# 3_3V_to_DDR4_VDD.net
KiCad netlist of a schematic drawn in Altium Designer
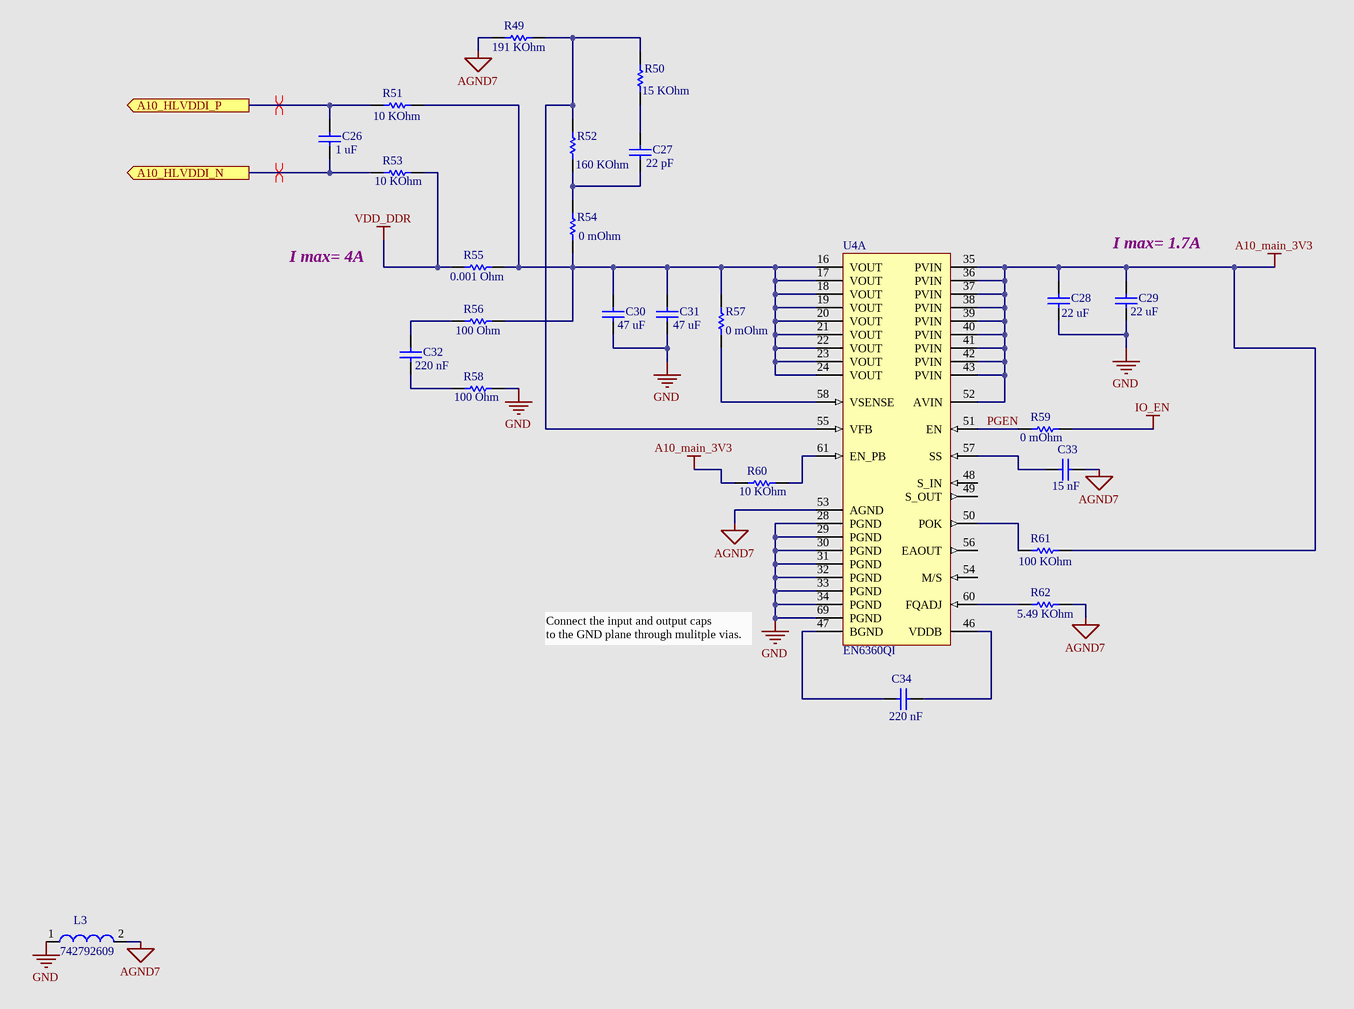
[diagram p0: 3.3V_to_DDR4_VDD.SchDoc]

(export (version "E")
  (design (tool "Eeschema 10.0.6"))
  (components
    (comp (ref "C26")
      (value "CGB2A1X5R1E105K033BC")
      (footprint "CAPC1005X33X10LL5")
      (description "Chip Capacitor, 1 uF, +/- 10%, 25 V, -55 to 85 degC, 0402 (1005 Metric), RoHS, Tape and Reel")
      (fields (field (name "TOLERANCE") "10%") (field (name "CAPACITANCE") "1 uF"))
      (libsource (lib "") (part "CAP-NP-2_1"))
    )
    (comp (ref "C27")
      (value "C1005C0G1H220J050BA")
      (footprint "CAPC1005X55X10LL05")
      (description "Chip Capacitor, 22 pF, +/- 5%, 50 V, -55 to 125 degC, 0402 (1005 Metric), RoHS, Tape and Reel")
      (fields (field (name "TOLERANCE") "5%") (field (name "CAPACITANCE") "22 pF"))
      (libsource (lib "Altium Content Vault") (part "CAP-NP-2"))
    )
    (comp (ref "C28")
      (value "GRM31CR61E226KE15L")
      (footprint "CAPC3216X180X55ML20T25")
      (description "Chip Capacitor, 22 uF, +/- 10%, 25 V, -55 to 85 degC, 1206 (3216 Metric), RoHS, Tape and Reel")
      (fields (field (name "TOLERANCE") "10%") (field (name "CAPACITANCE") "22 uF"))
      (libsource (lib "Altium Content Vault") (part "CAP-NP-2"))
    )
    (comp (ref "C29")
      (value "GRM31CR61E226KE15L")
      (footprint "CAPC3216X180X55ML20T25")
      (description "Chip Capacitor, 22 uF, +/- 10%, 25 V, -55 to 85 degC, 1206 (3216 Metric), RoHS, Tape and Reel")
      (fields (field (name "TOLERANCE") "10%") (field (name "CAPACITANCE") "22 uF"))
      (libsource (lib "Altium Content Vault") (part "CAP-NP-2"))
    )
    (comp (ref "C30")
      (value "C3216X5R1A476M160AB")
      (footprint "CAPC3216X180X20ML20")
      (description "Chip Capacitor, 47 uF, +/- 20%, 10 V, -55 to 85 degC, 1206 (3216 Metric), RoHS, Tape and Reel")
      (fields (field (name "TOLERANCE") "20%") (field (name "CAPACITANCE") "47 uF"))
      (libsource (lib "") (part "CAP-NP-2_1"))
    )
    (comp (ref "C31")
      (value "C3216X5R1A476M160AB")
      (footprint "CAPC3216X180X20ML20")
      (description "Chip Capacitor, 47 uF, +/- 20%, 10 V, -55 to 85 degC, 1206 (3216 Metric), RoHS, Tape and Reel")
      (fields (field (name "TOLERANCE") "20%") (field (name "CAPACITANCE") "47 uF"))
      (libsource (lib "") (part "CAP-NP-2_1"))
    )
    (comp (ref "C32")
      (value "GRM155R61A224KE19D")
      (footprint "CAPC1005X55X25NL05T10")
      (description "Chip Capacitor, 220 nF, +/- 10%, 10 V, -55 to 85 degC, 0402 (1005 Metric), RoHS, Tape and Reel")
      (fields
        (field (name "TOLERANCE") "10%")
        (field (name "CAPACITANCE") "220 nF")
        (field (name "MANUFACTURER") "Basic Passives")
      )
      (libsource (lib "Altium Content Vault") (part "CAP-NP-2"))
    )
    (comp (ref "C33")
      (value "VJ0402Y153JXQPW1BC")
      (footprint "CAPC1005X55X23ML05T8")
      (description "Chip Capacitor, 15 nF, +/- 5%, 10 V, -55 to 125 degC, 0402 (1005 Metric), RoHS, Tape and Reel")
      (fields (field (name "CAPACITANCE") "15 nF") (field (name "TOLERANCE") "5%"))
      (libsource (lib "Altium Content Vault") (part "CAP-NP-2"))
    )
    (comp (ref "C34")
      (value "GRM155R61A224KE19D")
      (footprint "CAPC1005X55X25NL05T10")
      (description "Chip Capacitor, 220 nF, +/- 10%, 10 V, -55 to 85 degC, 0402 (1005 Metric), RoHS, Tape and Reel")
      (fields
        (field (name "TOLERANCE") "10%")
        (field (name "CAPACITANCE") "220 nF")
        (field (name "MANUFACTURER") "Basic Passives")
      )
      (libsource (lib "Altium Content Vault") (part "CAP-NP-2"))
    )
    (comp (ref "L3")
      (value "742792609")
      (footprint "SMD-0603")
      (description "SMD EMI Suppression Ferrite Bead WE-CBF, Z = 30 Ohm")
      (libsource (lib "Altium Content Vault") (part "CMP-0220-00193-1"))
    )
    (comp (ref "R49")
      (value "CRCW0402191KFKED")
      (footprint "RESC1005X40X25LL05T05")
      (description "Chip Resistor, 191 KOhm, +/- 1%, 63 mW, -55 to 155 degC, 0402 (1005 Metric), RoHS, Tape and Reel")
      (fields
        (field (name "TOLERANCE") "1%")
        (field (name "RESISTANCE") "191 KOhm")
        (field (name "MANUFACTURER") "Basic Passives")
      )
      (libsource (lib "Altium Content Vault") (part "RES-2"))
    )
    (comp (ref "R50")
      (value "ERJ-2RKF1502X")
      (footprint "RESC1005X40X25ML05T05")
      (description "Chip Resistor, 15 KOhm, +/- 1%, 100 mW, -55 to 155 degC, 0402 (1005 Metric), RoHS, Tape and Reel")
      (fields
        (field (name "RESISTANCE") "15 KOhm")
        (field (name "TOLERANCE") "1%")
        (field (name "MANUFACTURER") "Basic Passives")
      )
      (libsource (lib "Altium Content Vault") (part "RES-2"))
    )
    (comp (ref "R51")
      (value "ERJ-2RKF1002X")
      (footprint "RESC1005X40X25NL05T05")
      (description "Chip Resistor, 10 KOhm, +/- 1%, 100 mW, -55 to 155 degC, 0402 (1005 Metric), RoHS, Tape and Reel")
      (fields
        (field (name "TOLERANCE") "1%")
        (field (name "RESISTANCE") "10 KOhm")
        (field (name "MANUFACTURER") "Basic Passives")
      )
      (libsource (lib "Altium Content Vault") (part "RES-2"))
    )
    (comp (ref "R52")
      (value "CRCW0402160KFKED")
      (footprint "RESC1005X40X25ML05T05")
      (description "Chip Resistor, 160 KOhm, +/- 1%, 63 mW, -55 to 155 degC, 0402 (1005 Metric), RoHS, Tape and Reel")
      (fields
        (field (name "TOLERANCE") "1%")
        (field (name "RESISTANCE") "160 KOhm")
        (field (name "MANUFACTURER") "Basic Passives")
      )
      (libsource (lib "Altium Content Vault") (part "RES-2"))
    )
    (comp (ref "R53")
      (value "ERJ-2RKF1002X")
      (footprint "RESC1005X40X25NL05T05")
      (description "Chip Resistor, 10 KOhm, +/- 1%, 100 mW, -55 to 155 degC, 0402 (1005 Metric), RoHS, Tape and Reel")
      (fields
        (field (name "TOLERANCE") "1%")
        (field (name "RESISTANCE") "10 KOhm")
        (field (name "MANUFACTURER") "Basic Passives")
      )
      (libsource (lib "Altium Content Vault") (part "RES-2"))
    )
    (comp (ref "R54")
      (value "ERJ-2GE0R00X")
      (footprint "RESC1005X40X25ML05T05")
      (description "Chip Resistor, 0 mOhm, +/- 5%, 100 mW, -55 to 155 degC, 0402 (1005 Metric), RoHS, Tape and Reel")
      (fields
        (field (name "TOLERANCE") "5%")
        (field (name "RESISTANCE") "0 mOhm")
        (field (name "MANUFACTURER") "Basic Passives")
      )
      (libsource (lib "Altium Content Vault") (part "RES-2"))
    )
    (comp (ref "R55")
      (value "WSLP12061L000FEA")
      (footprint "RESC3216X89X104LL25T25")
      (description "Chip Resistor, 0.001 Ohm, +/- 1%, 1 W, -65 to 170 degC, 1206 (3216 Metric), RoHS, Tape and Reel")
      (fields (field (name "TOLERANCE") "1%") (field (name "RESISTANCE") "0.001 Ohm"))
      (libsource (lib "Altium Content Vault") (part "RES-2"))
    )
    (comp (ref "R56")
      (value "ERJ-2RKF1000X")
      (footprint "RESC1005X40X25LL05T05")
      (description "Chip Resistor, 100 Ohm, +/- 1%, 100 mW, -55 to 155 degC, 0402 (1005 Metric), RoHS, Tape and Reel")
      (fields
        (field (name "TOLERANCE") "1%")
        (field (name "RESISTANCE") "100 Ohm")
        (field (name "MANUFACTURER") "Basic Passives")
      )
      (libsource (lib "Altium Content Vault") (part "RES-2"))
    )
    (comp (ref "R57")
      (value "ERJ-2GE0R00X")
      (footprint "RESC1005X40X25ML05T05")
      (description "Chip Resistor, 0 mOhm, +/- 5%, 100 mW, -55 to 155 degC, 0402 (1005 Metric), RoHS, Tape and Reel")
      (fields
        (field (name "TOLERANCE") "5%")
        (field (name "RESISTANCE") "0 mOhm")
        (field (name "MANUFACTURER") "Basic Passives")
      )
      (libsource (lib "Altium Content Vault") (part "RES-2"))
    )
    (comp (ref "R58")
      (value "ERJ-2RKF1000X")
      (footprint "RESC1005X40X25LL05T05")
      (description "Chip Resistor, 100 Ohm, +/- 1%, 100 mW, -55 to 155 degC, 0402 (1005 Metric), RoHS, Tape and Reel")
      (fields
        (field (name "TOLERANCE") "1%")
        (field (name "RESISTANCE") "100 Ohm")
        (field (name "MANUFACTURER") "Basic Passives")
      )
      (libsource (lib "Altium Content Vault") (part "RES-2"))
    )
    (comp (ref "R59")
      (value "ERJ-2GE0R00X")
      (footprint "RESC1005X40X25ML05T05")
      (description "Chip Resistor, 0 mOhm, +/- 5%, 100 mW, -55 to 155 degC, 0402 (1005 Metric), RoHS, Tape and Reel")
      (fields
        (field (name "TOLERANCE") "5%")
        (field (name "RESISTANCE") "0 mOhm")
        (field (name "MANUFACTURER") "Basic Passives")
      )
      (libsource (lib "Altium Content Vault") (part "RES-2"))
    )
    (comp (ref "R60")
      (value "ERJ-2RKF1002X")
      (footprint "RESC1005X40X25NL05T05")
      (description "Chip Resistor, 10 KOhm, +/- 1%, 100 mW, -55 to 155 degC, 0402 (1005 Metric), RoHS, Tape and Reel")
      (fields
        (field (name "TOLERANCE") "1%")
        (field (name "RESISTANCE") "10 KOhm")
        (field (name "MANUFACTURER") "Basic Passives")
      )
      (libsource (lib "Altium Content Vault") (part "RES-2"))
    )
    (comp (ref "R61")
      (value "ERJ-2RKF1003X")
      (footprint "RESC1005X40X25LL05T05")
      (description "Chip Resistor, 100 KOhm, +/- 1%, 100 mW, -55 to 155 degC, 0402 (1005 Metric), RoHS, Tape and Reel")
      (fields
        (field (name "RESISTANCE") "100 KOhm")
        (field (name "TOLERANCE") "1%")
        (field (name "MANUFACTURER") "Basic Passives")
      )
      (libsource (lib "Altium Content Vault") (part "RES-2"))
    )
    (comp (ref "R62")
      (value "ERJ-2RKF5491X")
      (footprint "RESC1005X40X25NL05T05")
      (description "Chip Resistor, 5.49 KOhm, +/- 1%, 100 mW, -55 to 155 degC, 0402 (1005 Metric), RoHS, Tape and Reel")
      (fields
        (field (name "TOLERANCE") "1%")
        (field (name "RESISTANCE") "5.49 KOhm")
        (field (name "MANUFACTURER") "Basic Passives")
      )
      (libsource (lib "Altium Content Vault") (part "RES-2"))
    )
    (comp (ref "U4")
      (value "EN6360QI")
      (footprint "ALTR-QFN-68_A-305_V")
      (libsource (lib "Altium Content Vault") (part "ALTR-EN6360QI-QFN68"))
    )
  )
  (nets
    (net (code "1") (name "/A10_HLVDDI_N") (class "Default")
      (node (ref "C26") (pin "1") (pinfunction "1_1") (pintype "passive"))
      (node (ref "R53") (pin "1") (pinfunction "1_1") (pintype "passive"))
    )
    (net (code "2") (name "/A10_HLVDDI_P") (class "Default")
      (node (ref "C26") (pin "2") (pinfunction "2_2") (pintype "passive"))
      (node (ref "R51") (pin "1") (pinfunction "1_1") (pintype "passive"))
    )
    (net (code "3") (name "/PGEN") (class "Default")
      (node (ref "R59") (pin "1") (pinfunction "1_1") (pintype "passive"))
      (node (ref "U4") (pin "51") (pinfunction "EN_51") (pintype "input"))
    )
    (net (code "4") (name "A10_main_3V3") (class "Default")
      (node (ref "C28") (pin "2") (pinfunction "2_2") (pintype "passive"))
      (node (ref "C29") (pin "2") (pinfunction "2_2") (pintype "passive"))
      (node (ref "R60") (pin "1") (pinfunction "1_1") (pintype "passive"))
      (node (ref "R61") (pin "2") (pinfunction "2_2") (pintype "passive"))
      (node (ref "U4") (pin "35") (pinfunction "PVIN_35") (pintype "power_in"))
      (node (ref "U4") (pin "36") (pinfunction "PVIN_36") (pintype "power_in"))
      (node (ref "U4") (pin "37") (pinfunction "PVIN_37") (pintype "power_in"))
      (node (ref "U4") (pin "38") (pinfunction "PVIN_38") (pintype "power_in"))
      (node (ref "U4") (pin "39") (pinfunction "PVIN_39") (pintype "power_in"))
      (node (ref "U4") (pin "40") (pinfunction "PVIN_40") (pintype "power_in"))
      (node (ref "U4") (pin "41") (pinfunction "PVIN_41") (pintype "power_in"))
      (node (ref "U4") (pin "42") (pinfunction "PVIN_42") (pintype "power_in"))
      (node (ref "U4") (pin "43") (pinfunction "PVIN_43") (pintype "power_in"))
      (node (ref "U4") (pin "52") (pinfunction "AVIN_52") (pintype "power_in"))
    )
    (net (code "5") (name "AGND7") (class "Default")
      (node (ref "C33") (pin "1") (pinfunction "1_1") (pintype "passive"))
      (node (ref "L3") (pin "2") (pinfunction "2_2") (pintype "passive"))
      (node (ref "R49") (pin "1") (pinfunction "1_1") (pintype "passive"))
      (node (ref "R62") (pin "2") (pinfunction "2_2") (pintype "passive"))
      (node (ref "U4") (pin "53") (pinfunction "AGND_53") (pintype "power_in"))
    )
    (net (code "6") (name "GND") (class "Default")
      (node (ref "C28") (pin "1") (pinfunction "1_1") (pintype "passive"))
      (node (ref "C29") (pin "1") (pinfunction "1_1") (pintype "passive"))
      (node (ref "C30") (pin "1") (pinfunction "1_1") (pintype "passive"))
      (node (ref "C31") (pin "1") (pinfunction "1_1") (pintype "passive"))
      (node (ref "L3") (pin "1") (pinfunction "1_1") (pintype "passive"))
      (node (ref "R58") (pin "1") (pinfunction "1_1") (pintype "passive"))
      (node (ref "U4") (pin "28") (pinfunction "PGND_28") (pintype "power_in"))
      (node (ref "U4") (pin "29") (pinfunction "PGND_29") (pintype "power_in"))
      (node (ref "U4") (pin "30") (pinfunction "PGND_30") (pintype "power_in"))
      (node (ref "U4") (pin "31") (pinfunction "PGND_31") (pintype "power_in"))
      (node (ref "U4") (pin "32") (pinfunction "PGND_32") (pintype "power_in"))
      (node (ref "U4") (pin "33") (pinfunction "PGND_33") (pintype "power_in"))
      (node (ref "U4") (pin "34") (pinfunction "PGND_34") (pintype "power_in"))
      (node (ref "U4") (pin "69") (pinfunction "PGND_69") (pintype "power_in"))
    )
    (net (code "7") (name "IO_EN") (class "Default")
      (node (ref "R59") (pin "2") (pinfunction "2_2") (pintype "passive"))
    )
    (net (code "8") (name "Net-(C27-Pad1)") (class "Default")
      (node (ref "C27") (pin "1") (pinfunction "1_1") (pintype "passive"))
      (node (ref "R52") (pin "1") (pinfunction "1_1") (pintype "passive"))
      (node (ref "R54") (pin "2") (pinfunction "2_2") (pintype "passive"))
    )
    (net (code "9") (name "Net-(C27-Pad2)") (class "Default")
      (node (ref "C27") (pin "2") (pinfunction "2_2") (pintype "passive"))
      (node (ref "R50") (pin "1") (pinfunction "1_1") (pintype "passive"))
    )
    (net (code "10") (name "Net-(C30-Pad2)") (class "Default")
      (node (ref "C30") (pin "2") (pinfunction "2_2") (pintype "passive"))
      (node (ref "C31") (pin "2") (pinfunction "2_2") (pintype "passive"))
      (node (ref "R51") (pin "2") (pinfunction "2_2") (pintype "passive"))
      (node (ref "R54") (pin "1") (pinfunction "1_1") (pintype "passive"))
      (node (ref "R55") (pin "2") (pinfunction "2_2") (pintype "passive"))
      (node (ref "R56") (pin "1") (pinfunction "1_1") (pintype "passive"))
      (node (ref "R57") (pin "2") (pinfunction "2_2") (pintype "passive"))
      (node (ref "U4") (pin "16") (pinfunction "VOUT_16") (pintype "power_in"))
      (node (ref "U4") (pin "17") (pinfunction "VOUT_17") (pintype "power_in"))
      (node (ref "U4") (pin "18") (pinfunction "VOUT_18") (pintype "power_in"))
      (node (ref "U4") (pin "19") (pinfunction "VOUT_19") (pintype "power_in"))
      (node (ref "U4") (pin "20") (pinfunction "VOUT_20") (pintype "power_in"))
      (node (ref "U4") (pin "21") (pinfunction "VOUT_21") (pintype "power_in"))
      (node (ref "U4") (pin "22") (pinfunction "VOUT_22") (pintype "power_in"))
      (node (ref "U4") (pin "23") (pinfunction "VOUT_23") (pintype "power_in"))
      (node (ref "U4") (pin "24") (pinfunction "VOUT_24") (pintype "power_in"))
    )
    (net (code "11") (name "Net-(C32-Pad1)") (class "Default")
      (node (ref "C32") (pin "1") (pinfunction "1_1") (pintype "passive"))
      (node (ref "R56") (pin "2") (pinfunction "2_2") (pintype "passive"))
    )
    (net (code "12") (name "Net-(C32-Pad2)") (class "Default")
      (node (ref "C32") (pin "2") (pinfunction "2_2") (pintype "passive"))
      (node (ref "R58") (pin "2") (pinfunction "2_2") (pintype "passive"))
    )
    (net (code "13") (name "Net-(U4A-BGND)") (class "Default")
      (node (ref "C34") (pin "1") (pinfunction "1_1") (pintype "passive"))
      (node (ref "U4") (pin "47") (pinfunction "BGND_47") (pintype "power_in"))
    )
    (net (code "14") (name "Net-(U4A-EN_PB)") (class "Default")
      (node (ref "R60") (pin "2") (pinfunction "2_2") (pintype "passive"))
      (node (ref "U4") (pin "61") (pinfunction "EN_PB_61") (pintype "input"))
    )
    (net (code "15") (name "Net-(U4A-FQADJ)") (class "Default")
      (node (ref "R62") (pin "1") (pinfunction "1_1") (pintype "passive"))
      (node (ref "U4") (pin "60") (pinfunction "FQADJ_60") (pintype "input"))
    )
    (net (code "16") (name "Net-(U4A-POK)") (class "Default")
      (node (ref "R61") (pin "1") (pinfunction "1_1") (pintype "passive"))
      (node (ref "U4") (pin "50") (pinfunction "POK_50") (pintype "output"))
    )
    (net (code "17") (name "Net-(U4A-SS)") (class "Default")
      (node (ref "C33") (pin "2") (pinfunction "2_2") (pintype "passive"))
      (node (ref "U4") (pin "57") (pinfunction "SS_57") (pintype "input"))
    )
    (net (code "18") (name "Net-(U4A-VDDB)") (class "Default")
      (node (ref "C34") (pin "2") (pinfunction "2_2") (pintype "passive"))
      (node (ref "U4") (pin "46") (pinfunction "VDDB_46") (pintype "power_in"))
    )
    (net (code "19") (name "Net-(U4A-VFB)") (class "Default")
      (node (ref "R49") (pin "2") (pinfunction "2_2") (pintype "passive"))
      (node (ref "R50") (pin "2") (pinfunction "2_2") (pintype "passive"))
      (node (ref "R52") (pin "2") (pinfunction "2_2") (pintype "passive"))
      (node (ref "U4") (pin "55") (pinfunction "VFB_55") (pintype "input"))
    )
    (net (code "20") (name "Net-(U4A-VSENSE)") (class "Default")
      (node (ref "R57") (pin "1") (pinfunction "1_1") (pintype "passive"))
      (node (ref "U4") (pin "58") (pinfunction "VSENSE_58") (pintype "input"))
    )
    (net (code "21") (name "VDD_DDR") (class "Default")
      (node (ref "R53") (pin "2") (pinfunction "2_2") (pintype "passive"))
      (node (ref "R55") (pin "1") (pinfunction "1_1") (pintype "passive"))
    )
    (net (code "22") (name "unconnected-(U4A-EAOUT-Pad56)") (class "Default")
      (node (ref "U4") (pin "56") (pinfunction "EAOUT_56") (pintype "output"))
    )
    (net (code "23") (name "unconnected-(U4A-M{slash}S-Pad54)") (class "Default")
      (node (ref "U4") (pin "54") (pinfunction "M/S_54") (pintype "input"))
    )
    (net (code "24") (name "unconnected-(U4A-S_IN-Pad48)") (class "Default")
      (node (ref "U4") (pin "48") (pinfunction "S_IN_48") (pintype "input"))
    )
    (net (code "25") (name "unconnected-(U4A-S_OUT-Pad49)") (class "Default")
      (node (ref "U4") (pin "49") (pinfunction "S_OUT_49") (pintype "output"))
    )
  )
)
